# Power-Management.net
KiCad netlist of a schematic drawn in Altium Designer
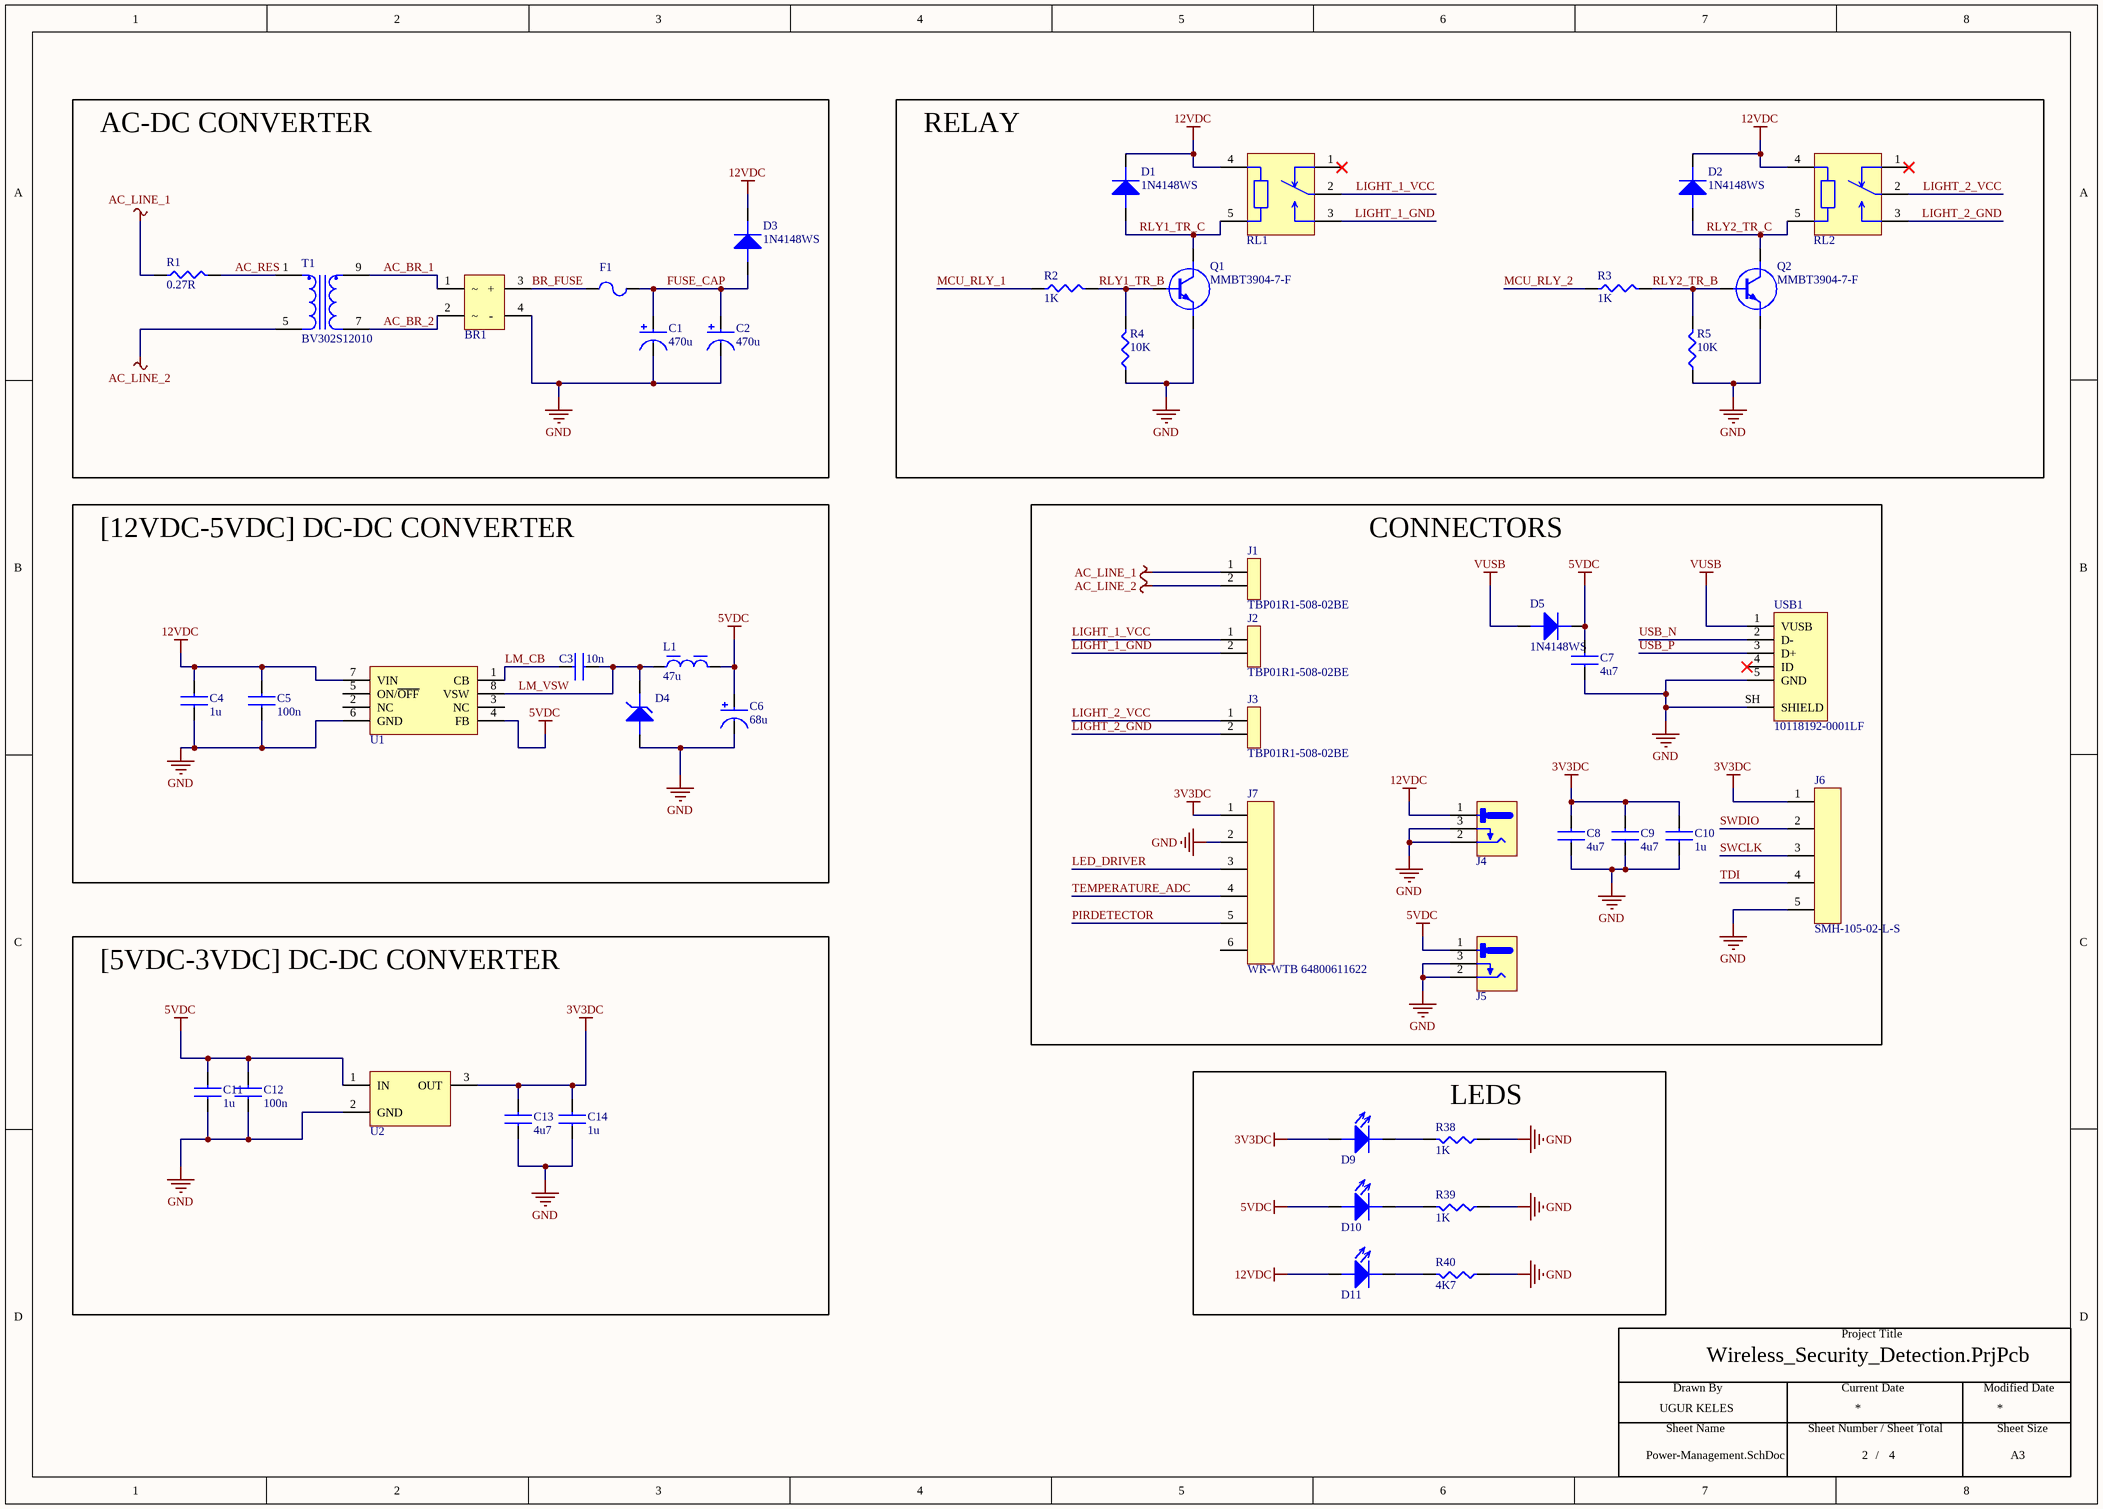
[diagram p0: Power-Management.SchDoc]

(export (version "E")
  (design (tool "Eeschema 10.0.6"))
  (components
    (comp (ref "BR1")
      (value "DB105S")
      (footprint "DB105S")
      (description "Bridge Rectifier Single Phase Standard 600 V Surface Mount DB-S")
      (fields (field (name "MANUFACTURER") "Sangdest Microelectronics") (field (name "DESIGNED BY") "UK"))
      (libsource (lib "UKLIB") (part "DB105S"))
    )
    (comp (ref "C1")
      (value "470u")
      (footprint "CAP ALUM RADIAL TH D10 L20 P5")
      (description "Radial Electrolytic Aluminium Capacitor, 470uF, 50VDC, 20%")
      (fields
        (field (name "MANUFACTURER") "KEMET")
        (field (name "MANUFACTURER PART NUMBER") "ESH477M050AH4AA")
        (field (name "DESIGNED BY") "UK")
      )
      (libsource (lib "UKLIB") (part "CAP ALUM 470uF RADIAL TH"))
    )
    (comp (ref "C2")
      (value "470u")
      (footprint "CAP ALUM RADIAL TH D10 L20 P5")
      (description "Radial Electrolytic Aluminium Capacitor, 470uF, 50VDC, 20%")
      (fields
        (field (name "MANUFACTURER") "KEMET")
        (field (name "MANUFACTURER PART NUMBER") "ESH477M050AH4AA")
        (field (name "DESIGNED BY") "UK")
      )
      (libsource (lib "UKLIB") (part "CAP ALUM 470uF RADIAL TH"))
    )
    (comp (ref "C3")
      (value "10n")
      (footprint "CAPACITOR 0603")
      (description "0603 16V X7R 10nF 10% multilayer ceramic capacitor")
      (fields
        (field (name "MANUFACTURER") "Walsin Technologies")
        (field (name "MANUFACTURER PART NUMBER") "0603B103K160CT")
        (field (name "DESIGNED BY") "UK")
      )
      (libsource (lib "UKLIB") (part "CAP CER 10nF 0603"))
    )
    (comp (ref "C4")
      (value "1u")
      (footprint "CAPACITOR 0805 - duplicate")
      (description "Multilayer Ceramic Capacitor, 1 uF, 50 V, ± 10%, X7R, 0805 [2012 Metric]")
      (fields
        (field (name "MANUFACTURER") "Samsung")
        (field (name "MANUFACTURER PART NUMBER") "CL21B105KBFNNNE")
        (field (name "DESIGNED BY") "UK")
      )
      (libsource (lib "UKLIB") (part "CAP CER 1uF 0805"))
    )
    (comp (ref "C5")
      (value "100n")
      (footprint "CAPACITOR 0805 - duplicate")
      (description "Multilayer Ceramic Capacitor, 0.1 uF, 50 V, ± 10%, X7R, 0805 [2012 Metric]")
      (fields
        (field (name "MANUFACTURER") "Samsung")
        (field (name "MANUFACTURER PART NUMBER") "CL21B104KBCNNNC")
        (field (name "DESIGNED BY") "UK")
      )
      (libsource (lib "UKLIB") (part "CAP CER 100nF 0805"))
    )
    (comp (ref "C6")
      (value "68u")
      (footprint "CAP ALUM RADIAL SMD D6.3 L7.7 P1.8")
      (description "Cap Aluminum Lytic 68uF 35V 20%( 6.3 X 7.7mm) SMD 0.34 Ohm 280mA 2000h 105C T/R")
      (fields
        (field (name "MANUFACTURER") "KEMET")
        (field (name "MANUFACTURER PART NUMBER") "EEV686M035A9HAA")
        (field (name "DESIGNED BY") "UK")
      )
      (libsource (lib "UKLIB") (part "CAP ALUM 68UF RADIAL SMD"))
    )
    (comp (ref "C7")
      (value "4u7")
      (footprint "CAPACITOR 0805 - duplicate")
      (description "Multilayer Ceramic Capacitor, 4.7 uF, 25 V, ± 10%, X5R, 0805 [2012 Metric]")
      (fields
        (field (name "MANUFACTURER") "Samsung")
        (field (name "MANUFACTURER PART NUMBER") "CL21A475KAQNNNE")
        (field (name "DESIGNED BY") "UK")
      )
      (libsource (lib "UKLIB") (part "CAP CER 4.7uF 0805"))
    )
    (comp (ref "C8")
      (value "4u7")
      (footprint "CAPACITOR 0805 - duplicate")
      (description "Multilayer Ceramic Capacitor, 4.7 uF, 25 V, ± 10%, X5R, 0805 [2012 Metric]")
      (fields
        (field (name "MANUFACTURER") "Samsung")
        (field (name "MANUFACTURER PART NUMBER") "CL21A475KAQNNNE")
        (field (name "DESIGNED BY") "UK")
      )
      (libsource (lib "UKLIB") (part "CAP CER 4.7uF 0805"))
    )
    (comp (ref "C9")
      (value "4u7")
      (footprint "CAPACITOR 0805 - duplicate")
      (description "Multilayer Ceramic Capacitor, 4.7 uF, 25 V, ± 10%, X5R, 0805 [2012 Metric]")
      (fields
        (field (name "MANUFACTURER") "Samsung")
        (field (name "MANUFACTURER PART NUMBER") "CL21A475KAQNNNE")
        (field (name "DESIGNED BY") "UK")
      )
      (libsource (lib "UKLIB") (part "CAP CER 4.7uF 0805"))
    )
    (comp (ref "C10")
      (value "1u")
      (footprint "CAPACITOR 0805 - duplicate")
      (description "Multilayer Ceramic Capacitor, 1 uF, 50 V, ± 10%, X7R, 0805 [2012 Metric]")
      (fields
        (field (name "MANUFACTURER") "Samsung")
        (field (name "MANUFACTURER PART NUMBER") "CL21B105KBFNNNE")
        (field (name "DESIGNED BY") "UK")
      )
      (libsource (lib "UKLIB") (part "CAP CER 1uF 0805"))
    )
    (comp (ref "C11")
      (value "1u")
      (footprint "CAPACITOR 0805 - duplicate")
      (description "Multilayer Ceramic Capacitor, 1 uF, 50 V, ± 10%, X7R, 0805 [2012 Metric]")
      (fields
        (field (name "MANUFACTURER") "Samsung")
        (field (name "MANUFACTURER PART NUMBER") "CL21B105KBFNNNE")
        (field (name "DESIGNED BY") "UK")
      )
      (libsource (lib "UKLIB") (part "CAP CER 1uF 0805"))
    )
    (comp (ref "C12")
      (value "100n")
      (footprint "Capacitor 0603")
      (description "Multilayer Ceramic Capacitor, 0.1 uF, 50 V, ± 10%, X7R, 0603 [1608 Metric]")
      (fields
        (field (name "MANUFACTURER") "KEMET")
        (field (name "MANUFACTURER PART NUMBER") "C0603C104K5RACTU")
        (field (name "DESIGNED BY") "UK")
      )
      (libsource (lib "UKLIB") (part "CAP CER 100nF 0603"))
    )
    (comp (ref "C13")
      (value "4u7")
      (footprint "CAPACITOR 0805 - duplicate")
      (description "Multilayer Ceramic Capacitor, 4.7 uF, 25 V, ± 10%, X5R, 0805 [2012 Metric]")
      (fields
        (field (name "MANUFACTURER") "Samsung")
        (field (name "MANUFACTURER PART NUMBER") "CL21A475KAQNNNE")
        (field (name "DESIGNED BY") "UK")
      )
      (libsource (lib "UKLIB") (part "CAP CER 4.7uF 0805"))
    )
    (comp (ref "C14")
      (value "1u")
      (footprint "CAPACITOR 0805 - duplicate")
      (description "Multilayer Ceramic Capacitor, 1 uF, 50 V, ± 10%, X7R, 0805 [2012 Metric]")
      (fields
        (field (name "MANUFACTURER") "Samsung")
        (field (name "MANUFACTURER PART NUMBER") "CL21B105KBFNNNE")
        (field (name "DESIGNED BY") "UK")
      )
      (libsource (lib "UKLIB") (part "CAP CER 1uF 0805"))
    )
    (comp (ref "D1")
      (value "1N4148WS")
      (footprint "SOD-323F")
      (description "Diode Ultra Fast Recovery Rectifier 75V 0.15A 2-Pin SOD-323F T/R")
      (fields (field (name "MANUFACTURER") "ON Semiconductor / Fairchild") (field (name "DESIGNED BY") "UK"))
      (libsource (lib "UKLIB") (part "1N4148WS"))
    )
    (comp (ref "D2")
      (value "1N4148WS")
      (footprint "SOD-323F")
      (description "Diode Ultra Fast Recovery Rectifier 75V 0.15A 2-Pin SOD-323F T/R")
      (fields (field (name "MANUFACTURER") "ON Semiconductor / Fairchild") (field (name "DESIGNED BY") "UK"))
      (libsource (lib "UKLIB") (part "1N4148WS"))
    )
    (comp (ref "D3")
      (value "1N4148WS")
      (footprint "SOD-323F")
      (description "Diode Ultra Fast Recovery Rectifier 75V 0.15A 2-Pin SOD-323F T/R")
      (fields (field (name "MANUFACTURER") "ON Semiconductor / Fairchild") (field (name "DESIGNED BY") "UK"))
      (libsource (lib "UKLIB") (part "1N4148WS"))
    )
    (comp (ref "D4")
      (value "1SMB5919BT3G")
      (footprint "SMB")
      (description "Diode Zener Single 5.6V 5% 550mW Automotive 2-Pin SMB T/R")
      (fields (field (name "MANUFACTURER") "ON Semiconductor") (field (name "DESIGNED BY") "UK"))
      (libsource (lib "UKLIB") (part "1SMB5919BT3G"))
    )
    (comp (ref "D5")
      (value "1N4148WS")
      (footprint "SOD-323F")
      (description "Diode Ultra Fast Recovery Rectifier 75V 0.15A 2-Pin SOD-323F T/R")
      (fields (field (name "MANUFACTURER") "ON Semiconductor / Fairchild") (field (name "DESIGNED BY") "UK"))
      (libsource (lib "UKLIB") (part "1N4148WS"))
    )
    (comp (ref "D9")
      (value "LTST-C171GKT")
      (footprint "LED GREEN 0805")
      (description "LED Low-Power Uni-Color Green 565nm 2.1V 2-Pin Chip LED T/R")
      (fields (field (name "MANUFACTURER") "Vishay Lite-On") (field (name "DESIGNED BY") "UK"))
      (libsource (lib "UKLIB") (part "LED GREEN 0805"))
    )
    (comp (ref "D10")
      (value "LTST-C171GKT")
      (footprint "LED GREEN 0805")
      (description "LED Low-Power Uni-Color Green 565nm 2.1V 2-Pin Chip LED T/R")
      (fields (field (name "MANUFACTURER") "Vishay Lite-On") (field (name "DESIGNED BY") "UK"))
      (libsource (lib "UKLIB") (part "LED GREEN 0805"))
    )
    (comp (ref "D11")
      (value "LTST-C171GKT")
      (footprint "LED GREEN 0805")
      (description "LED Low-Power Uni-Color Green 565nm 2.1V 2-Pin Chip LED T/R")
      (fields (field (name "MANUFACTURER") "Vishay Lite-On") (field (name "DESIGNED BY") "UK"))
      (libsource (lib "UKLIB") (part "LED GREEN 0805"))
    )
    (comp (ref "F1")
      (value "3413.0216.22")
      (footprint "3413.0216.22")
      (description "Fuse Chip Fast Acting 1A 32V SMD Solder Pad 1206 Glass T/R VDE/cULus")
      (fields (field (name "MANUFACTURER") "Schurter") (field (name "DESIGNED BY") "UK"))
      (libsource (lib "UKLIB") (part "3413.0216.22"))
    )
    (comp (ref "J1")
      (value "TBP01R1-508-02BE")
      (footprint "2P TH TERMINAL 5.08 MALE")
      (description "2 Poles, Pluggable, Receptacle, Horizontal, 5.08 Pitch, Terminal Block Connector")
      (fields (field (name "MANUFACTURER") "CUI Devices") (field (name "DESIGNED BY") "UK"))
      (libsource (lib "UKLIB") (part "2P TH TERMINAL 5.08 MALE"))
    )
    (comp (ref "J2")
      (value "TBP01R1-508-02BE")
      (footprint "2P TH TERMINAL 5.08 MALE")
      (description "2 Poles, Pluggable, Receptacle, Horizontal, 5.08 Pitch, Terminal Block Connector")
      (fields (field (name "MANUFACTURER") "CUI Devices") (field (name "DESIGNED BY") "UK"))
      (libsource (lib "UKLIB") (part "2P TH TERMINAL 5.08 MALE"))
    )
    (comp (ref "J3")
      (value "TBP01R1-508-02BE")
      (footprint "2P TH TERMINAL 5.08 MALE")
      (description "2 Poles, Pluggable, Receptacle, Horizontal, 5.08 Pitch, Terminal Block Connector")
      (fields (field (name "MANUFACTURER") "CUI Devices") (field (name "DESIGNED BY") "UK"))
      (libsource (lib "UKLIB") (part "2P TH TERMINAL 5.08 MALE"))
    )
    (comp (ref "J4")
      (value "PJ-037AH-SMT-TR")
      (footprint "JACK")
      (description "2.0 x 6.3 mm, 5.0 A, Horizontal, Surface Mount (SMT), Dc Power Jack Connector")
      (fields (field (name "MANUFACTURER") "CUI") (field (name "DESIGNED BY") "UK"))
      (libsource (lib "UKLIB") (part "PJ-037AH-SMT-TR"))
    )
    (comp (ref "J5")
      (value "PJ-037AH-SMT-TR")
      (footprint "JACK")
      (description "2.0 x 6.3 mm, 5.0 A, Horizontal, Surface Mount (SMT), Dc Power Jack Connector")
      (fields (field (name "MANUFACTURER") "CUI") (field (name "DESIGNED BY") "UK"))
      (libsource (lib "UKLIB") (part "PJ-037AH-SMT-TR"))
    )
    (comp (ref "J6")
      (value "SMH-105-02-L-S")
      (footprint "5P TH CONN 2.54 FEMALE HEADER")
      (description "PCB Receptacle, Board-to-Board, 2.54 mm, 1 Rows, 5 Contacts, Surface Mount, SMH")
      (fields (field (name "MANUFACTURER") "Samtec") (field (name "DESIGNED BY") "UK"))
      (libsource (lib "UKLIB") (part "5P SMD CONN 2.54 FEMALE HEADER"))
    )
    (comp (ref "J7")
      (value "WR-WTB 64800611622")
      (footprint "6P SMD TERMINAL 1.50 MALE")
      (description "WR-WTB Wire-to-Board Connectors 1.50 mm")
      (fields
        (field (name "MANUFACTURER") "Wurth Electronics")
        (field (name "MANUFACTURER PART NUMBER") "64800611622")
        (field (name "DESIGNED BY") "UK")
      )
      (libsource (lib "UKLIB") (part "6P SMD TERMINAL 1.50 MALE"))
    )
    (comp (ref "L1")
      (value "47u")
      (footprint "IND 1212")
      (description "Power Inductor, Aec-Q200, 47Uh, 0.39A Rohs Compliant: Yes ¦Wurth Elektronik 78438335470")
      (fields
        (field (name "MANUFACTURER") "Wurth Electronics")
        (field (name "MANUFACTURER PART NUMBER") "78438335470")
        (field (name "DESIGNED BY") "UK")
      )
      (libsource (lib "UKLIB") (part "IND 47uH"))
    )
    (comp (ref "Q1")
      (value "MMBT3904-7-F")
      (footprint "SOT-23F")
      (description "Transistor General Purpose BJT NPN 40 Volt 0.2A Automotive 3-Pin SOT-23")
      (fields (field (name "MANUFACTURER") "Diodes Zetex") (field (name "DESIGNED BY") "UK"))
      (libsource (lib "UKLIB") (part "MMBT3904-7-F"))
    )
    (comp (ref "Q2")
      (value "MMBT3904-7-F")
      (footprint "SOT-23F")
      (description "Transistor General Purpose BJT NPN 40 Volt 0.2A Automotive 3-Pin SOT-23")
      (fields (field (name "MANUFACTURER") "Diodes Zetex") (field (name "DESIGNED BY") "UK"))
      (libsource (lib "UKLIB") (part "MMBT3904-7-F"))
    )
    (comp (ref "R1")
      (value "0.27R")
      (footprint "RES 5WD27 AXIAL")
      (description "270 mOhms ±5% 5W Through Hole Resistor Axial Wirewound")
      (fields (field (name "TOLERANCE") "±5%") (field (name "DESIGNED BY") "UK"))
      (libsource (lib "UKLIB") (part "RES 0.27R AXIAL"))
    )
    (comp (ref "R2")
      (value "1K")
      (footprint "Resistor 0603")
      (description "SMD Chip Resistor, 1 kOhm, ± 1%, 100 mW, 0603 [1608 Metric], Thick Film, General Purpose")
      (fields
        (field (name "MANUFACTURER") "Yageo")
        (field (name "MANUFACTURER PART NUMBER") "RC0603FR-071KL")
        (field (name "DESIGNED BY") "UK")
      )
      (libsource (lib "UKLIB") (part "RES 1K 0603"))
    )
    (comp (ref "R3")
      (value "1K")
      (footprint "Resistor 0603")
      (description "SMD Chip Resistor, 1 kOhm, ± 1%, 100 mW, 0603 [1608 Metric], Thick Film, General Purpose")
      (fields
        (field (name "MANUFACTURER") "Yageo")
        (field (name "MANUFACTURER PART NUMBER") "RC0603FR-071KL")
        (field (name "DESIGNED BY") "UK")
      )
      (libsource (lib "UKLIB") (part "RES 1K 0603"))
    )
    (comp (ref "R4")
      (value "10K")
      (footprint "Resistor 0603")
      (description "SMD Chip Resistor, 10 kOhm, ± 1%, 100 mW, 0603 [1608 Metric], Thick Film, General Purpose")
      (fields
        (field (name "MANUFACTURER") "Yageo")
        (field (name "MANUFACTURER PART NUMBER") "RC0603FR-0710KL")
        (field (name "DESIGNED BY") "UK")
      )
      (libsource (lib "UKLIB") (part "RES 10K 0603"))
    )
    (comp (ref "R5")
      (value "10K")
      (footprint "Resistor 0603")
      (description "SMD Chip Resistor, 10 kOhm, ± 1%, 100 mW, 0603 [1608 Metric], Thick Film, General Purpose")
      (fields
        (field (name "MANUFACTURER") "Yageo")
        (field (name "MANUFACTURER PART NUMBER") "RC0603FR-0710KL")
        (field (name "DESIGNED BY") "UK")
      )
      (libsource (lib "UKLIB") (part "RES 10K 0603"))
    )
    (comp (ref "R38")
      (value "1K")
      (footprint "Resistor 0603")
      (description "SMD Chip Resistor, 1 kOhm, ± 1%, 100 mW, 0603 [1608 Metric], Thick Film, General Purpose")
      (fields
        (field (name "MANUFACTURER") "Yageo")
        (field (name "MANUFACTURER PART NUMBER") "RC0603FR-071KL")
        (field (name "DESIGNED BY") "UK")
      )
      (libsource (lib "UKLIB") (part "RES 1K 0603"))
    )
    (comp (ref "R39")
      (value "1K")
      (footprint "Resistor 0603")
      (description "SMD Chip Resistor, 1 kOhm, ± 1%, 100 mW, 0603 [1608 Metric], Thick Film, General Purpose")
      (fields
        (field (name "MANUFACTURER") "Yageo")
        (field (name "MANUFACTURER PART NUMBER") "RC0603FR-071KL")
        (field (name "DESIGNED BY") "UK")
      )
      (libsource (lib "UKLIB") (part "RES 1K 0603"))
    )
    (comp (ref "R40")
      (value "4K7")
      (footprint "Resistor 0603")
      (description "SMD Chip Resistor, 4.7 kOhm, ± 5%, 100 mW, 0603 [1608 Metric], Thick Film, General Purpose")
      (fields
        (field (name "MANUFACTURER") "Yageo")
        (field (name "MANUFACTURER PART NUMBER") "RC0603JR-074K7L")
        (field (name "DESIGNED BY") "UK")
      )
      (libsource (lib "UKLIB") (part "RES 4K7 0603"))
    )
    (comp (ref "RL1")
      (value "ALQ112")
      (footprint "ALQ112")
      (description "Electromechanical Relay 12VDC 360Ohm 10(NO)/3(NC)A SPDT (( 20mm 10mm 16mm)) THT Power Relay")
      (fields (field (name "MANUFACTURER") "Panasonic") (field (name "DESIGNED BY") "UK"))
      (libsource (lib "UKLIB") (part "ALQ112"))
    )
    (comp (ref "RL2")
      (value "ALQ112")
      (footprint "ALQ112")
      (description "Electromechanical Relay 12VDC 360Ohm 10(NO)/3(NC)A SPDT (( 20mm 10mm 16mm)) THT Power Relay")
      (fields (field (name "MANUFACTURER") "Panasonic") (field (name "DESIGNED BY") "UK"))
      (libsource (lib "UKLIB") (part "ALQ112"))
    )
    (comp (ref "T1")
      (value "BV302S12010")
      (footprint "BV302S12010")
      (description "Sealed Transformer EI30/10.5")
      (fields (field (name "MANUFACTURER") "Zettler Magnetics") (field (name "DESIGNED BY") "UK"))
      (libsource (lib "UKLIB") (part "BV302S12010"))
    )
    (comp (ref "U1")
      (value "LM2675MX-12/NOPB")
      (footprint "SOIC-8")
      (description "Buck Switching Regulator IC Positive Fixed 12V 1 Output 1A 8-SOIC (0.154\", 3.90mm Width)")
      (fields (field (name "MANUFACTURER") "TI National Semiconductor") (field (name "DESIGNED BY") "UK"))
      (libsource (lib "UKLIB") (part "LM2675MX-12/NOPB"))
    )
    (comp (ref "U2")
      (value "AP7361-33E-13")
      (footprint "SOT223/SOT223R")
      (description "Linear Voltage Regulator IC Positive Fixed 1 Output 1A SOT-223-3")
      (fields (field (name "MANUFACTURER") "Diodes") (field (name "DESIGNED BY") "UK"))
      (libsource (lib "UKLIB") (part "AP7361-33E-13"))
    )
    (comp (ref "USB1")
      (value "10118192-0001LF")
      (footprint "USB2.0 MICRO B SMD")
      (description "CONN USB MICRO B RECPT SMT R/A")
      (fields (field (name "MANUFACTURER") "Amphenol ICC / FCI") (field (name "DESIGNED BY") "UK"))
      (libsource (lib "UKLIB") (part "Micro B USB Connector"))
    )
  )
  (nets
    (net (code "1") (name "/AC_BR_1") (class "Default")
      (node (ref "BR1") (pin "1") (pinfunction "~_1") (pintype "passive"))
      (node (ref "T1") (pin "9") (pinfunction "9_9") (pintype "passive"))
    )
    (net (code "2") (name "/AC_BR_2") (class "Default")
      (node (ref "BR1") (pin "2") (pinfunction "~_2") (pintype "passive"))
      (node (ref "T1") (pin "7") (pinfunction "7_7") (pintype "passive"))
    )
    (net (code "3") (name "/AC_RES") (class "Default")
      (node (ref "R1") (pin "2") (pinfunction "2_2") (pintype "passive"))
      (node (ref "T1") (pin "1") (pinfunction "1_1") (pintype "passive"))
    )
    (net (code "4") (name "/BR_FUSE") (class "Default")
      (node (ref "BR1") (pin "3") (pinfunction "+_3") (pintype "passive"))
      (node (ref "F1") (pin "1") (pinfunction "1_1") (pintype "passive"))
    )
    (net (code "5") (name "/FUSE_CAP") (class "Default")
      (node (ref "C1") (pin "1") (pinfunction "1_1") (pintype "passive"))
      (node (ref "C2") (pin "1") (pinfunction "1_1") (pintype "passive"))
      (node (ref "D3") (pin "1") (pinfunction "A_1") (pintype "passive"))
      (node (ref "F1") (pin "2") (pinfunction "2_2") (pintype "passive"))
    )
    (net (code "6") (name "/LED_DRIVER") (class "Default")
      (node (ref "J7") (pin "3") (pinfunction "3_3") (pintype "passive"))
    )
    (net (code "7") (name "/LIGHT_1_GND") (class "Default")
      (node (ref "J2") (pin "2") (pinfunction "2_2") (pintype "passive"))
      (node (ref "RL1") (pin "3") (pinfunction "3_3") (pintype "passive"))
    )
    (net (code "8") (name "/LIGHT_1_VCC") (class "Default")
      (node (ref "J2") (pin "1") (pinfunction "1_1") (pintype "passive"))
      (node (ref "RL1") (pin "2") (pinfunction "2_2") (pintype "passive"))
    )
    (net (code "9") (name "/LIGHT_2_GND") (class "Default")
      (node (ref "J3") (pin "2") (pinfunction "2_2") (pintype "passive"))
      (node (ref "RL2") (pin "3") (pinfunction "3_3") (pintype "passive"))
    )
    (net (code "10") (name "/LIGHT_2_VCC") (class "Default")
      (node (ref "J3") (pin "1") (pinfunction "1_1") (pintype "passive"))
      (node (ref "RL2") (pin "2") (pinfunction "2_2") (pintype "passive"))
    )
    (net (code "11") (name "/LM_CB") (class "Default")
      (node (ref "C3") (pin "1") (pinfunction "1_1") (pintype "passive"))
      (node (ref "U1") (pin "1") (pinfunction "CB_1") (pintype "passive"))
    )
    (net (code "12") (name "/LM_VSW") (class "Default")
      (node (ref "C3") (pin "2") (pinfunction "2_2") (pintype "passive"))
      (node (ref "D4") (pin "2") (pinfunction "C_2") (pintype "passive"))
      (node (ref "L1") (pin "1") (pinfunction "1_1") (pintype "passive"))
      (node (ref "U1") (pin "8") (pinfunction "VSW_8") (pintype "passive"))
    )
    (net (code "13") (name "/MCU_RLY_1") (class "Default")
      (node (ref "R2") (pin "1") (pinfunction "1_1") (pintype "passive"))
    )
    (net (code "14") (name "/MCU_RLY_2") (class "Default")
      (node (ref "R3") (pin "1") (pinfunction "1_1") (pintype "passive"))
    )
    (net (code "15") (name "/PIRDETECTOR") (class "Default")
      (node (ref "J7") (pin "5") (pinfunction "5_5") (pintype "passive"))
    )
    (net (code "16") (name "/RLY1_TR_B") (class "Default")
      (node (ref "Q1") (pin "1") (pinfunction "B_1") (pintype "passive"))
      (node (ref "R2") (pin "2") (pinfunction "2_2") (pintype "passive"))
      (node (ref "R4") (pin "2") (pinfunction "2_2") (pintype "passive"))
    )
    (net (code "17") (name "/RLY1_TR_C") (class "Default")
      (node (ref "D1") (pin "1") (pinfunction "A_1") (pintype "passive"))
      (node (ref "Q1") (pin "3") (pinfunction "C_3") (pintype "passive"))
      (node (ref "RL1") (pin "5") (pinfunction "5_5") (pintype "passive"))
    )
    (net (code "18") (name "/RLY2_TR_B") (class "Default")
      (node (ref "Q2") (pin "1") (pinfunction "B_1") (pintype "passive"))
      (node (ref "R3") (pin "2") (pinfunction "2_2") (pintype "passive"))
      (node (ref "R5") (pin "2") (pinfunction "2_2") (pintype "passive"))
    )
    (net (code "19") (name "/RLY2_TR_C") (class "Default")
      (node (ref "D2") (pin "1") (pinfunction "A_1") (pintype "passive"))
      (node (ref "Q2") (pin "3") (pinfunction "C_3") (pintype "passive"))
      (node (ref "RL2") (pin "5") (pinfunction "5_5") (pintype "passive"))
    )
    (net (code "20") (name "/SWCLK") (class "Default")
      (node (ref "J6") (pin "3") (pinfunction "3_3") (pintype "passive"))
    )
    (net (code "21") (name "/SWDIO") (class "Default")
      (node (ref "J6") (pin "2") (pinfunction "2_2") (pintype "passive"))
    )
    (net (code "22") (name "/TDI") (class "Default")
      (node (ref "J6") (pin "4") (pinfunction "4_4") (pintype "passive"))
    )
    (net (code "23") (name "/TEMPERATURE_ADC") (class "Default")
      (node (ref "J7") (pin "4") (pinfunction "4_4") (pintype "passive"))
    )
    (net (code "24") (name "/USB_N") (class "Default")
      (node (ref "USB1") (pin "2") (pinfunction "D-_2") (pintype "passive"))
    )
    (net (code "25") (name "/USB_P") (class "Default")
      (node (ref "USB1") (pin "3") (pinfunction "D+_3") (pintype "passive"))
    )
    (net (code "26") (name "3V3DC") (class "Default")
      (node (ref "C10") (pin "2") (pinfunction "2_2") (pintype "passive"))
      (node (ref "C13") (pin "2") (pinfunction "2_2") (pintype "passive"))
      (node (ref "C14") (pin "2") (pinfunction "2_2") (pintype "passive"))
      (node (ref "C8") (pin "2") (pinfunction "2_2") (pintype "passive"))
      (node (ref "C9") (pin "2") (pinfunction "2_2") (pintype "passive"))
      (node (ref "D9") (pin "1") (pinfunction "A_1") (pintype "passive"))
      (node (ref "J6") (pin "1") (pinfunction "1_1") (pintype "passive"))
      (node (ref "J7") (pin "1") (pinfunction "1_1") (pintype "passive"))
      (node (ref "U2") (pin "3") (pinfunction "OUT_3") (pintype "passive"))
    )
    (net (code "27") (name "5VDC") (class "Default")
      (node (ref "C11") (pin "2") (pinfunction "2_2") (pintype "passive"))
      (node (ref "C12") (pin "2") (pinfunction "2_2") (pintype "passive"))
      (node (ref "C6") (pin "1") (pinfunction "1_1") (pintype "passive"))
      (node (ref "C7") (pin "2") (pinfunction "2_2") (pintype "passive"))
      (node (ref "D10") (pin "1") (pinfunction "A_1") (pintype "passive"))
      (node (ref "D5") (pin "2") (pinfunction "C_2") (pintype "passive"))
      (node (ref "J5") (pin "1") (pinfunction "VCC_1") (pintype "passive"))
      (node (ref "L1") (pin "2") (pinfunction "2_2") (pintype "passive"))
      (node (ref "U1") (pin "4") (pinfunction "FB_4") (pintype "passive"))
      (node (ref "U2") (pin "1") (pinfunction "IN_1") (pintype "passive"))
    )
    (net (code "28") (name "12VDC") (class "Default")
      (node (ref "C4") (pin "2") (pinfunction "2_2") (pintype "passive"))
      (node (ref "C5") (pin "2") (pinfunction "2_2") (pintype "passive"))
      (node (ref "D1") (pin "2") (pinfunction "C_2") (pintype "passive"))
      (node (ref "D11") (pin "1") (pinfunction "A_1") (pintype "passive"))
      (node (ref "D2") (pin "2") (pinfunction "C_2") (pintype "passive"))
      (node (ref "D3") (pin "2") (pinfunction "C_2") (pintype "passive"))
      (node (ref "J4") (pin "1") (pinfunction "VCC_1") (pintype "passive"))
      (node (ref "RL1") (pin "4") (pinfunction "4_4") (pintype "passive"))
      (node (ref "RL2") (pin "4") (pinfunction "4_4") (pintype "passive"))
      (node (ref "U1") (pin "7") (pinfunction "VIN_7") (pintype "passive"))
    )
    (net (code "29") (name "AC_LINE_1") (class "Default")
      (node (ref "J1") (pin "1") (pinfunction "1_1") (pintype "passive"))
      (node (ref "R1") (pin "1") (pinfunction "1_1") (pintype "passive"))
    )
    (net (code "30") (name "AC_LINE_2") (class "Default")
      (node (ref "J1") (pin "2") (pinfunction "2_2") (pintype "passive"))
      (node (ref "T1") (pin "5") (pinfunction "5_5") (pintype "passive"))
    )
    (net (code "31") (name "GND") (class "Default")
      (node (ref "BR1") (pin "4") (pinfunction "-_4") (pintype "passive"))
      (node (ref "C1") (pin "2") (pinfunction "2_2") (pintype "passive"))
      (node (ref "C10") (pin "1") (pinfunction "1_1") (pintype "passive"))
      (node (ref "C11") (pin "1") (pinfunction "1_1") (pintype "passive"))
      (node (ref "C12") (pin "1") (pinfunction "1_1") (pintype "passive"))
      (node (ref "C13") (pin "1") (pinfunction "1_1") (pintype "passive"))
      (node (ref "C14") (pin "1") (pinfunction "1_1") (pintype "passive"))
      (node (ref "C2") (pin "2") (pinfunction "2_2") (pintype "passive"))
      (node (ref "C4") (pin "1") (pinfunction "1_1") (pintype "passive"))
      (node (ref "C5") (pin "1") (pinfunction "1_1") (pintype "passive"))
      (node (ref "C6") (pin "2") (pinfunction "2_2") (pintype "passive"))
      (node (ref "C7") (pin "1") (pinfunction "1_1") (pintype "passive"))
      (node (ref "C8") (pin "1") (pinfunction "1_1") (pintype "passive"))
      (node (ref "C9") (pin "1") (pinfunction "1_1") (pintype "passive"))
      (node (ref "D4") (pin "1") (pinfunction "A_1") (pintype "passive"))
      (node (ref "J4") (pin "2") (pinfunction "GND_2") (pintype "passive"))
      (node (ref "J4") (pin "3") (pinfunction "SH_3") (pintype "passive"))
      (node (ref "J5") (pin "2") (pinfunction "GND_2") (pintype "passive"))
      (node (ref "J5") (pin "3") (pinfunction "SH_3") (pintype "passive"))
      (node (ref "J6") (pin "5") (pinfunction "5_5") (pintype "passive"))
      (node (ref "J7") (pin "2") (pinfunction "2_2") (pintype "passive"))
      (node (ref "Q1") (pin "2") (pinfunction "E_2") (pintype "passive"))
      (node (ref "Q2") (pin "2") (pinfunction "E_2") (pintype "passive"))
      (node (ref "R38") (pin "1") (pinfunction "1_1") (pintype "passive"))
      (node (ref "R39") (pin "1") (pinfunction "1_1") (pintype "passive"))
      (node (ref "R4") (pin "1") (pinfunction "1_1") (pintype "passive"))
      (node (ref "R40") (pin "1") (pinfunction "1_1") (pintype "passive"))
      (node (ref "R5") (pin "1") (pinfunction "1_1") (pintype "passive"))
      (node (ref "U1") (pin "6") (pinfunction "GND_6") (pintype "passive"))
      (node (ref "U2") (pin "2") (pinfunction "GND_2") (pintype "passive"))
      (node (ref "USB1") (pin "5") (pinfunction "GND_5") (pintype "passive"))
      (node (ref "USB1") (pin "SH") (pinfunction "SHIELD_SH") (pintype "passive"))
    )
    (net (code "32") (name "Net-(D9-C)") (class "Default")
      (node (ref "D9") (pin "2") (pinfunction "C_2") (pintype "passive"))
      (node (ref "R38") (pin "2") (pinfunction "2_2") (pintype "passive"))
    )
    (net (code "33") (name "Net-(D10-C)") (class "Default")
      (node (ref "D10") (pin "2") (pinfunction "C_2") (pintype "passive"))
      (node (ref "R39") (pin "2") (pinfunction "2_2") (pintype "passive"))
    )
    (net (code "34") (name "Net-(D11-C)") (class "Default")
      (node (ref "D11") (pin "2") (pinfunction "C_2") (pintype "passive"))
      (node (ref "R40") (pin "2") (pinfunction "2_2") (pintype "passive"))
    )
    (net (code "35") (name "VUSB") (class "Default")
      (node (ref "D5") (pin "1") (pinfunction "A_1") (pintype "passive"))
      (node (ref "USB1") (pin "1") (pinfunction "VUSB_1") (pintype "passive"))
    )
    (net (code "36") (name "unconnected-(J7-Pad6)") (class "Default")
      (node (ref "J7") (pin "6") (pinfunction "6_6") (pintype "passive"))
    )
    (net (code "37") (name "unconnected-(RL1-Pad1)") (class "Default")
      (node (ref "RL1") (pin "1") (pinfunction "1_1") (pintype "passive+no_connect"))
    )
    (net (code "38") (name "unconnected-(RL2-Pad1)") (class "Default")
      (node (ref "RL2") (pin "1") (pinfunction "1_1") (pintype "passive+no_connect"))
    )
    (net (code "39") (name "unconnected-(U1-NC-Pad2)") (class "Default")
      (node (ref "U1") (pin "2") (pinfunction "NC_2") (pintype "passive"))
    )
    (net (code "40") (name "unconnected-(U1-NC-Pad3)") (class "Default")
      (node (ref "U1") (pin "3") (pinfunction "NC_3") (pintype "passive"))
    )
    (net (code "41") (name "unconnected-(U1-ON{slash}~{OFF}-Pad5)") (class "Default")
      (node (ref "U1") (pin "5") (pinfunction "ON/~{OFF}_5") (pintype "passive"))
    )
    (net (code "42") (name "unconnected-(USB1-ID-Pad4)") (class "Default")
      (node (ref "USB1") (pin "4") (pinfunction "ID_4") (pintype "passive+no_connect"))
    )
  )
)
